# NIP_-DRIVE.net
KiCad netlist of a schematic drawn in Altium Designer
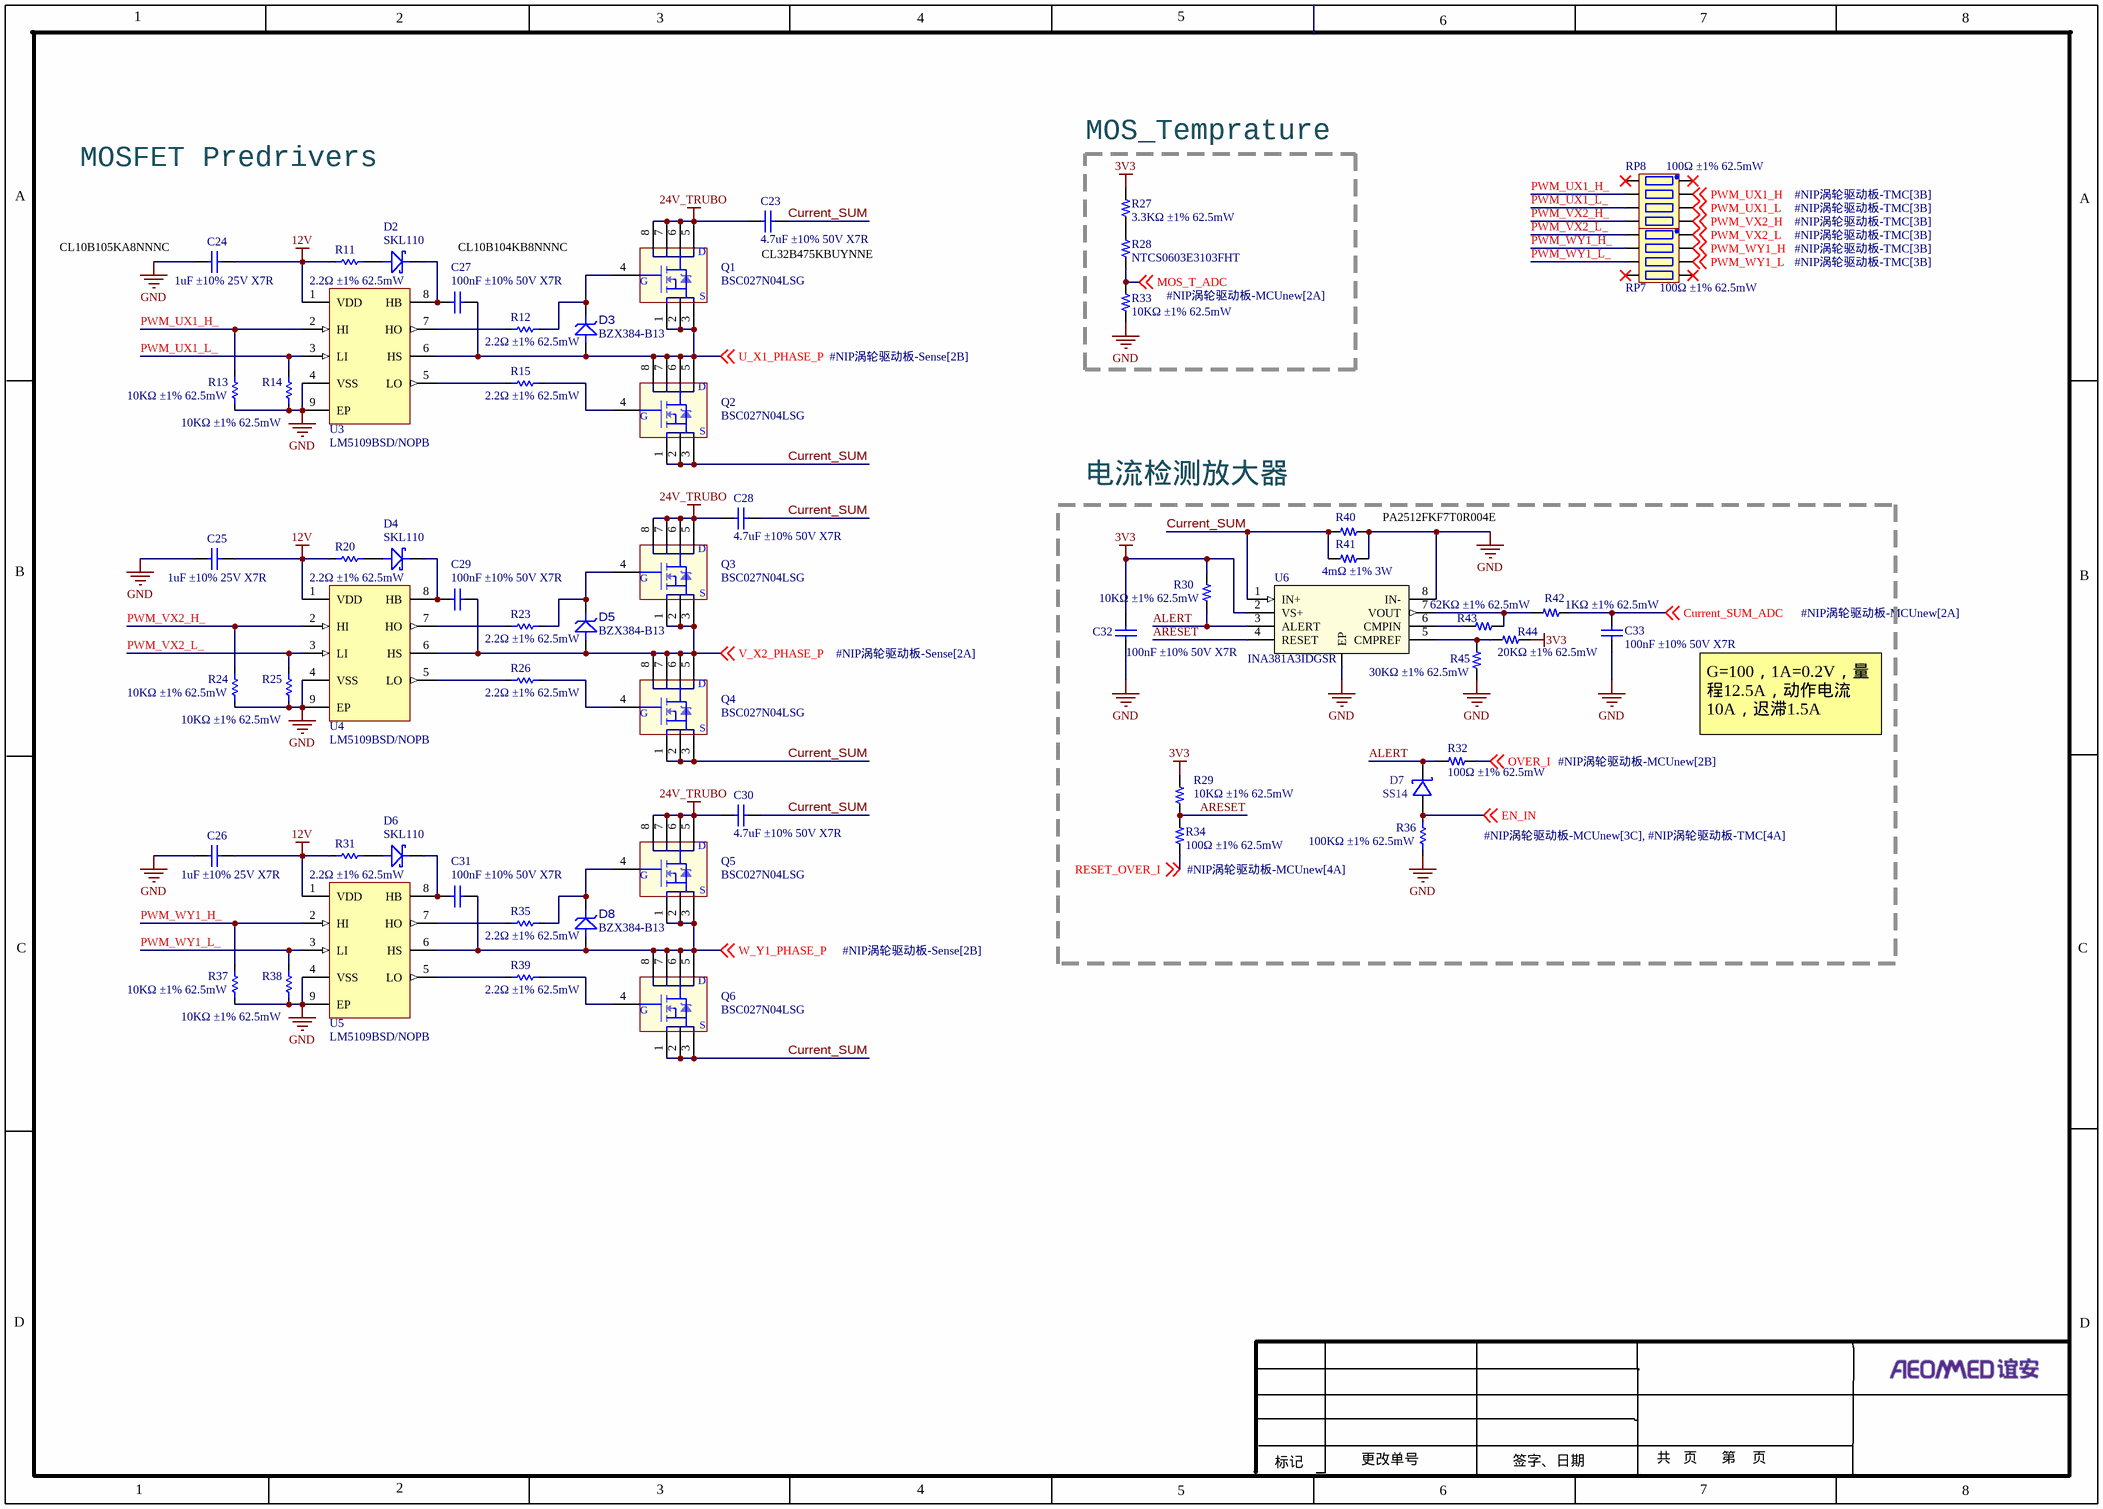
[diagram p0: #NIP涡轮驱动板-DRIVE.SchDoc]

(export (version "E")
  (design (tool "Eeschema 10.0.6"))
  (components
    (comp (ref "C23")
      (value "4.7uF ±10% 50V X7R")
      (footprint "C-1210")
      (description "CL32B475KBUYNNE")
      (libsource (lib "Device") (part "C-1210"))
    )
    (comp (ref "C24")
      (value "1uF ±10% 25V X7R")
      (footprint "C0603")
      (description "CL10B105KA8NNNC")
      (fields (field (name "PUBLISHER") "Altium Limited"))
      (libsource (lib "Component") (part "Cap"))
    )
    (comp (ref "C25")
      (value "1uF ±10% 25V X7R")
      (footprint "C0603")
      (description "CL10B105KA8NNNC")
      (fields (field (name "PUBLISHER") "Altium Limited"))
      (libsource (lib "Component") (part "Cap"))
    )
    (comp (ref "C26")
      (value "1uF ±10% 25V X7R")
      (footprint "C0603")
      (description "CL10B105KA8NNNC")
      (fields (field (name "PUBLISHER") "Altium Limited"))
      (libsource (lib "Component") (part "Cap"))
    )
    (comp (ref "C27")
      (value "100nF ±10% 50V X7R")
      (footprint "C-0603")
      (description "CL10B104KB8NNNC")
      (libsource (lib "Device") (part "C-0603"))
    )
    (comp (ref "C28")
      (value "4.7uF ±10% 50V X7R")
      (footprint "C-1210")
      (description "CL32B475KBUYNNE")
      (libsource (lib "Device") (part "C-1210"))
    )
    (comp (ref "C29")
      (value "100nF ±10% 50V X7R")
      (footprint "C-0603")
      (description "CL10B104KB8NNNC")
      (libsource (lib "Device") (part "C-0603"))
    )
    (comp (ref "C30")
      (value "4.7uF ±10% 50V X7R")
      (footprint "C-1210")
      (description "CL32B475KBUYNNE")
      (libsource (lib "Device") (part "C-1210"))
    )
    (comp (ref "C31")
      (value "100nF ±10% 50V X7R")
      (footprint "C-0603")
      (description "CL10B104KB8NNNC")
      (libsource (lib "Device") (part "C-0603"))
    )
    (comp (ref "C32")
      (value "100nF ±10% 50V X7R")
      (footprint "C0402")
      (description "Capacitor")
      (fields (field (name "PUBLISHER") "Altium Limited"))
      (libsource (lib "Component") (part "Cap"))
    )
    (comp (ref "C33")
      (value "100nF ±10% 50V X7R")
      (footprint "C0402")
      (description "Capacitor")
      (fields (field (name "PUBLISHER") "Altium Limited"))
      (libsource (lib "Component") (part "Cap"))
    )
    (comp (ref "D2")
      (value "SKL110")
      (footprint "SODFL370X140-2N")
      (description "品牌：DIOTEC，型号：SKL110，1A，100V，ROHS")
      (fields (field (name "MANUFACTURER") "Diotec  Semiconductor"))
      (libsource (lib "altium-import") (part "root_2_DIO-SCHOTTKY_"))
    )
    (comp (ref "D3")
      (value "BZX384-B13")
      (footprint "SOD2512X100N")
      (description "品牌：NXP，型号：BZX384-B13，13V，SOD-323，ROHS")
      (fields (field (name "MANUFACTURER") "Nexperia"))
      (libsource (lib "BLDC") (part "ZENER"))
    )
    (comp (ref "D4")
      (value "SKL110")
      (footprint "SODFL370X140-2N")
      (description "品牌：DIOTEC，型号：SKL110，1A，100V，ROHS")
      (fields (field (name "MANUFACTURER") "Diotec  Semiconductor"))
      (libsource (lib "altium-import") (part "root_2_DIO-SCHOTTKY_"))
    )
    (comp (ref "D5")
      (value "BZX384-B13")
      (footprint "SOD2512X100N")
      (description "品牌：NXP，型号：BZX384-B13，13V，SOD-323，ROHS")
      (fields (field (name "MANUFACTURER") "Nexperia"))
      (libsource (lib "BLDC") (part "ZENER"))
    )
    (comp (ref "D6")
      (value "SKL110")
      (footprint "SODFL370X140-2N")
      (description "品牌：DIOTEC，型号：SKL110，1A，100V，ROHS")
      (fields (field (name "MANUFACTURER") "Diotec  Semiconductor"))
      (libsource (lib "altium-import") (part "root_2_DIO-SCHOTTKY_"))
    )
    (comp (ref "D7")
      (value "SS14")
      (footprint "SOD-123_L2.7-W1.6-LS3.7-RD")
      (description "直流反向耐压(Vr):40V;平均整流电流(Io):3A;正向压降(Vf):500mV@3A;")
      (fields (field (name "MANUFACTURER") "DIODES(美台)") (field (name "MANUFACTURER PART") "B340A-13-F"))
      (libsource (lib "Component") (part "Diode_Schottky"))
    )
    (comp (ref "D8")
      (value "BZX384-B13")
      (footprint "SOD2512X100N")
      (description "品牌：NXP，型号：BZX384-B13，13V，SOD-323，ROHS")
      (fields (field (name "MANUFACTURER") "Nexperia"))
      (libsource (lib "BLDC") (part "ZENER"))
    )
    (comp (ref "Q1")
      (value "BSC027N04LSG")
      (footprint "PG-TDSON-8")
      (description "品牌：INFINEON，型号： BSC027N04LSG，40V，100A，ROHS")
      (libsource (lib "IC") (part "BSC027N04LS"))
    )
    (comp (ref "Q2")
      (value "BSC027N04LSG")
      (footprint "PG-TDSON-8")
      (description "品牌：INFINEON，型号： BSC027N04LSG，40V，100A，ROHS")
      (libsource (lib "IC") (part "BSC027N04LS"))
    )
    (comp (ref "Q3")
      (value "BSC027N04LSG")
      (footprint "PG-TDSON-8")
      (description "品牌：INFINEON，型号： BSC027N04LSG，40V，100A，ROHS")
      (libsource (lib "IC") (part "BSC027N04LS"))
    )
    (comp (ref "Q4")
      (value "BSC027N04LSG")
      (footprint "PG-TDSON-8")
      (description "品牌：INFINEON，型号： BSC027N04LSG，40V，100A，ROHS")
      (libsource (lib "IC") (part "BSC027N04LS"))
    )
    (comp (ref "Q5")
      (value "BSC027N04LSG")
      (footprint "PG-TDSON-8")
      (description "品牌：INFINEON，型号： BSC027N04LSG，40V，100A，ROHS")
      (libsource (lib "IC") (part "BSC027N04LS"))
    )
    (comp (ref "Q6")
      (value "BSC027N04LSG")
      (footprint "PG-TDSON-8")
      (description "品牌：INFINEON，型号： BSC027N04LSG，40V，100A，ROHS")
      (libsource (lib "IC") (part "BSC027N04LS"))
    )
    (comp (ref "R11")
      (value "2.2Ω ±1% 62.5mW")
      (footprint "R0402")
      (description "Resistor")
      (fields (field (name "PUBLISHER") "Altium Limited"))
      (libsource (lib "Component") (part "Res_0402"))
    )
    (comp (ref "R12")
      (value "2.2Ω ±1% 62.5mW")
      (footprint "R0402")
      (description "Resistor")
      (fields (field (name "PUBLISHER") "Altium Limited"))
      (libsource (lib "Component") (part "Res"))
    )
    (comp (ref "R13")
      (value "10KΩ ±1% 62.5mW")
      (footprint "R0402")
      (description "Resistor")
      (fields (field (name "PUBLISHER") "Altium Limited"))
      (libsource (lib "Component") (part "Res"))
    )
    (comp (ref "R14")
      (value "10KΩ ±1% 62.5mW")
      (footprint "R0402")
      (description "Resistor")
      (fields (field (name "PUBLISHER") "Altium Limited"))
      (libsource (lib "Component") (part "Res"))
    )
    (comp (ref "R15")
      (value "2.2Ω ±1% 62.5mW")
      (footprint "R0402")
      (description "Resistor")
      (fields (field (name "PUBLISHER") "Altium Limited"))
      (libsource (lib "Component") (part "Res"))
    )
    (comp (ref "R20")
      (value "2.2Ω ±1% 62.5mW")
      (footprint "R0402")
      (description "Resistor")
      (fields (field (name "PUBLISHER") "Altium Limited"))
      (libsource (lib "Component") (part "Res_0402"))
    )
    (comp (ref "R23")
      (value "2.2Ω ±1% 62.5mW")
      (footprint "R0402")
      (description "Resistor")
      (fields (field (name "PUBLISHER") "Altium Limited"))
      (libsource (lib "Component") (part "Res"))
    )
    (comp (ref "R24")
      (value "10KΩ ±1% 62.5mW")
      (footprint "R0402")
      (description "Resistor")
      (fields (field (name "PUBLISHER") "Altium Limited"))
      (libsource (lib "Component") (part "Res"))
    )
    (comp (ref "R25")
      (value "10KΩ ±1% 62.5mW")
      (footprint "R0402")
      (description "Resistor")
      (fields (field (name "PUBLISHER") "Altium Limited"))
      (libsource (lib "Component") (part "Res"))
    )
    (comp (ref "R26")
      (value "2.2Ω ±1% 62.5mW")
      (footprint "R0402")
      (description "Resistor")
      (fields (field (name "PUBLISHER") "Altium Limited"))
      (libsource (lib "Component") (part "Res"))
    )
    (comp (ref "R27")
      (value "3.3KΩ ±1% 62.5mW")
      (footprint "R0402")
      (libsource (lib "Device") (part "R-0603"))
    )
    (comp (ref "R28")
      (value "NTCS0603E3103FHT")
      (footprint "R-0603")
      (description "品牌：VISHAY，型号：NTCS0603E3103FHT，10K@25℃, 1%，B=3960,ROHS")
      (libsource (lib "Device") (part "R-0603"))
    )
    (comp (ref "R29")
      (value "10KΩ ±1% 62.5mW")
      (footprint "R0402")
      (libsource (lib "Device") (part "R-0603"))
    )
    (comp (ref "R30")
      (value "10KΩ ±1% 62.5mW")
      (footprint "R0402")
      (libsource (lib "Device") (part "R-0603"))
    )
    (comp (ref "R31")
      (value "2.2Ω ±1% 62.5mW")
      (footprint "R0402")
      (description "Resistor")
      (fields (field (name "PUBLISHER") "Altium Limited"))
      (libsource (lib "Component") (part "Res_0402"))
    )
    (comp (ref "R32")
      (value "100Ω ±1% 62.5mW")
      (footprint "R0402")
      (libsource (lib "Device") (part "R-0603"))
    )
    (comp (ref "R33")
      (value "10KΩ ±1% 62.5mW")
      (footprint "R0402")
      (libsource (lib "Device") (part "R-0603"))
    )
    (comp (ref "R34")
      (value "100Ω ±1% 62.5mW")
      (footprint "R0402")
      (libsource (lib "Device") (part "R-0603"))
    )
    (comp (ref "R35")
      (value "2.2Ω ±1% 62.5mW")
      (footprint "R0402")
      (description "Resistor")
      (fields (field (name "PUBLISHER") "Altium Limited"))
      (libsource (lib "Component") (part "Res"))
    )
    (comp (ref "R36")
      (value "100KΩ ±1% 62.5mW")
      (footprint "R0402")
      (description "RC0402FR-07100KL")
      (fields (field (name "PUBLISHER") "Altium Limited"))
      (libsource (lib "Component") (part "Res_0402"))
    )
    (comp (ref "R37")
      (value "10KΩ ±1% 62.5mW")
      (footprint "R0402")
      (description "Resistor")
      (fields (field (name "PUBLISHER") "Altium Limited"))
      (libsource (lib "Component") (part "Res"))
    )
    (comp (ref "R38")
      (value "10KΩ ±1% 62.5mW")
      (footprint "R0402")
      (description "Resistor")
      (fields (field (name "PUBLISHER") "Altium Limited"))
      (libsource (lib "Component") (part "Res"))
    )
    (comp (ref "R39")
      (value "2.2Ω ±1% 62.5mW")
      (footprint "R0402")
      (description "Resistor")
      (fields (field (name "PUBLISHER") "Altium Limited"))
      (libsource (lib "Component") (part "Res"))
    )
    (comp (ref "R40")
      (value "4mΩ ±1% 3W")
      (footprint "R-2512_4PIN")
      (description "PA2512FKF7T0R004E")
      (libsource (lib "Device") (part "R-2512"))
    )
    (comp (ref "R41")
      (value "4mΩ ±1% 3W")
      (footprint "R-2512_4PIN")
      (description "PA2512FKF7T0R004E")
      (libsource (lib "Device") (part "R-2512"))
    )
    (comp (ref "R42") (value "1KΩ ±1% 62.5mW") (footprint "R0402") (libsource (lib "Device") (part "R-0603")))
    (comp (ref "R43")
      (value "62KΩ ±1% 62.5mW")
      (footprint "R0402")
      (libsource (lib "Device") (part "R-0603"))
    )
    (comp (ref "R44")
      (value "20KΩ ±1% 62.5mW")
      (footprint "R0402")
      (libsource (lib "Device") (part "R-0603"))
    )
    (comp (ref "R45")
      (value "30KΩ ±1% 62.5mW")
      (footprint "R0402")
      (libsource (lib "Device") (part "R-0603"))
    )
    (comp (ref "RP7")
      (value "100Ω ±1% 62.5mW")
      (footprint "RES-ARRAY-SMD_0402-8P-L2.0-W1.0-BL")
      (libsource (lib "Device") (part "RP-0603"))
    )
    (comp (ref "RP8")
      (value "100Ω ±1% 62.5mW")
      (footprint "RES-ARRAY-SMD_0402-8P-L2.0-W1.0-BL")
      (libsource (lib "Device") (part "RP-0603"))
    )
    (comp (ref "U3")
      (value "LM5109BSD/NOPB")
      (footprint "PSON80P400X80_HS-9N")
      (description "品牌：TI，型号：LM5109BSD/NOPB，ROHS")
      (fields (field (name "MANUFACTURER") "Texas Instruments"))
      (libsource (lib "BLDC") (part "LM5109"))
    )
    (comp (ref "U4")
      (value "LM5109BSD/NOPB")
      (footprint "PSON80P400X80_HS-9N")
      (description "品牌：TI，型号：LM5109BSD/NOPB，ROHS")
      (fields (field (name "MANUFACTURER") "Texas Instruments"))
      (libsource (lib "BLDC") (part "LM5109"))
    )
    (comp (ref "U5")
      (value "LM5109BSD/NOPB")
      (footprint "PSON80P400X80_HS-9N")
      (description "品牌：TI，型号：LM5109BSD/NOPB，ROHS")
      (fields (field (name "MANUFACTURER") "Texas Instruments"))
      (libsource (lib "BLDC") (part "LM5109"))
    )
    (comp (ref "U6")
      (value "INA381A3IDGSR")
      (footprint "WSON-8_L2.0-W2.0-P0.50-BL-EP0.9")
      (description "品牌：TI，型号：INA381A1IDGSR，ROHS")
      (fields (field (name "COPYRIGHT") "Copyright (C) 2022 Ultra Librarian. All rights reserved."))
      (libsource (lib "all") (part "INA381A2IDSGR"))
    )
  )
  (nets
    (net (code "1") (name "/ALERT") (class "Default")
      (node (ref "D7") (pin "1") (pinfunction "K_1") (pintype "passive"))
      (node (ref "R30") (pin "2") (pinfunction "2_2") (pintype "passive"))
      (node (ref "R32") (pin "1") (pinfunction "1_1") (pintype "passive"))
      (node (ref "U6") (pin "3") (pinfunction "ALERT_3") (pintype "passive"))
    )
    (net (code "2") (name "/ARESET") (class "Default")
      (node (ref "R29") (pin "2") (pinfunction "2_2") (pintype "passive"))
      (node (ref "R34") (pin "1") (pinfunction "1_1") (pintype "passive"))
      (node (ref "U6") (pin "4") (pinfunction "RESET_4") (pintype "passive"))
    )
    (net (code "3") (name "/Current_SUM") (class "Default")
      (node (ref "C23") (pin "1") (pinfunction "1_1") (pintype "passive"))
      (node (ref "C28") (pin "1") (pinfunction "1_1") (pintype "passive"))
      (node (ref "C30") (pin "1") (pinfunction "1_1") (pintype "passive"))
      (node (ref "Q2") (pin "1") (pinfunction "S_1") (pintype "passive"))
      (node (ref "Q2") (pin "2") (pinfunction "S_2") (pintype "passive"))
      (node (ref "Q2") (pin "3") (pinfunction "S_3") (pintype "passive"))
      (node (ref "Q4") (pin "1") (pinfunction "S_1") (pintype "passive"))
      (node (ref "Q4") (pin "2") (pinfunction "S_2") (pintype "passive"))
      (node (ref "Q4") (pin "3") (pinfunction "S_3") (pintype "passive"))
      (node (ref "Q6") (pin "1") (pinfunction "S_1") (pintype "passive"))
      (node (ref "Q6") (pin "2") (pinfunction "S_2") (pintype "passive"))
      (node (ref "Q6") (pin "3") (pinfunction "S_3") (pintype "passive"))
      (node (ref "R40") (pin "2") (pinfunction "2_2") (pintype "passive"))
      (node (ref "R41") (pin "2") (pinfunction "2_2") (pintype "passive"))
      (node (ref "U6") (pin "1") (pinfunction "IN+_1") (pintype "input"))
    )
    (net (code "4") (name "/PWM_UX1_H_") (class "Default")
      (node (ref "R13") (pin "2") (pinfunction "2_2") (pintype "passive"))
      (node (ref "RP8") (pin "7") (pinfunction "7_7") (pintype "passive"))
      (node (ref "U3") (pin "2") (pinfunction "HI_2") (pintype "input"))
    )
    (net (code "5") (name "/PWM_UX1_L_") (class "Default")
      (node (ref "R14") (pin "2") (pinfunction "2_2") (pintype "passive"))
      (node (ref "RP8") (pin "6") (pinfunction "6_6") (pintype "passive"))
      (node (ref "U3") (pin "3") (pinfunction "LI_3") (pintype "input"))
    )
    (net (code "6") (name "/PWM_VX2_H_") (class "Default")
      (node (ref "R24") (pin "2") (pinfunction "2_2") (pintype "passive"))
      (node (ref "RP8") (pin "5") (pinfunction "5_5") (pintype "passive"))
      (node (ref "U4") (pin "2") (pinfunction "HI_2") (pintype "input"))
    )
    (net (code "7") (name "/PWM_VX2_L_") (class "Default")
      (node (ref "R25") (pin "2") (pinfunction "2_2") (pintype "passive"))
      (node (ref "RP7") (pin "8") (pinfunction "8_8") (pintype "passive"))
      (node (ref "U4") (pin "3") (pinfunction "LI_3") (pintype "input"))
    )
    (net (code "8") (name "/PWM_WY1_H_") (class "Default")
      (node (ref "R37") (pin "2") (pinfunction "2_2") (pintype "passive"))
      (node (ref "RP7") (pin "7") (pinfunction "7_7") (pintype "passive"))
      (node (ref "U5") (pin "2") (pinfunction "HI_2") (pintype "input"))
    )
    (net (code "9") (name "/PWM_WY1_L_") (class "Default")
      (node (ref "R38") (pin "2") (pinfunction "2_2") (pintype "passive"))
      (node (ref "RP7") (pin "6") (pinfunction "6_6") (pintype "passive"))
      (node (ref "U5") (pin "3") (pinfunction "LI_3") (pintype "input"))
    )
    (net (code "10") (name "3V3") (class "Default")
      (node (ref "C32") (pin "1") (pinfunction "1_1") (pintype "passive"))
      (node (ref "R27") (pin "2") (pinfunction "2_2") (pintype "passive"))
      (node (ref "R29") (pin "1") (pinfunction "1_1") (pintype "passive"))
      (node (ref "R30") (pin "1") (pinfunction "1_1") (pintype "passive"))
      (node (ref "R44") (pin "2") (pinfunction "2_2") (pintype "passive"))
      (node (ref "U6") (pin "2") (pinfunction "VS+_2") (pintype "passive"))
    )
    (net (code "11") (name "12V") (class "Default")
      (node (ref "C24") (pin "1") (pinfunction "1_1") (pintype "passive"))
      (node (ref "C25") (pin "1") (pinfunction "1_1") (pintype "passive"))
      (node (ref "C26") (pin "1") (pinfunction "1_1") (pintype "passive"))
      (node (ref "R11") (pin "1") (pinfunction "1_1") (pintype "passive"))
      (node (ref "R20") (pin "1") (pinfunction "1_1") (pintype "passive"))
      (node (ref "R31") (pin "1") (pinfunction "1_1") (pintype "passive"))
      (node (ref "U3") (pin "1") (pinfunction "VDD_1") (pintype "power_in"))
      (node (ref "U4") (pin "1") (pinfunction "VDD_1") (pintype "power_in"))
      (node (ref "U5") (pin "1") (pinfunction "VDD_1") (pintype "power_in"))
    )
    (net (code "12") (name "24V_TRUBO") (class "Default")
      (node (ref "C23") (pin "2") (pinfunction "2_2") (pintype "passive"))
      (node (ref "C28") (pin "2") (pinfunction "2_2") (pintype "passive"))
      (node (ref "C30") (pin "2") (pinfunction "2_2") (pintype "passive"))
      (node (ref "Q1") (pin "5") (pinfunction "D_5") (pintype "passive"))
      (node (ref "Q1") (pin "6") (pinfunction "D_6") (pintype "passive"))
      (node (ref "Q1") (pin "7") (pinfunction "D_7") (pintype "passive"))
      (node (ref "Q1") (pin "8") (pinfunction "D_8") (pintype "passive"))
      (node (ref "Q3") (pin "5") (pinfunction "D_5") (pintype "passive"))
      (node (ref "Q3") (pin "6") (pinfunction "D_6") (pintype "passive"))
      (node (ref "Q3") (pin "7") (pinfunction "D_7") (pintype "passive"))
      (node (ref "Q3") (pin "8") (pinfunction "D_8") (pintype "passive"))
      (node (ref "Q5") (pin "5") (pinfunction "D_5") (pintype "passive"))
      (node (ref "Q5") (pin "6") (pinfunction "D_6") (pintype "passive"))
      (node (ref "Q5") (pin "7") (pinfunction "D_7") (pintype "passive"))
      (node (ref "Q5") (pin "8") (pinfunction "D_8") (pintype "passive"))
    )
    (net (code "13") (name "Current_SUM_ADC") (class "Default")
      (node (ref "C33") (pin "2") (pinfunction "2_2") (pintype "passive"))
      (node (ref "R42") (pin "2") (pinfunction "2_2") (pintype "passive"))
    )
    (net (code "14") (name "EN_IN") (class "Default")
      (node (ref "D7") (pin "2") (pinfunction "A_2") (pintype "passive"))
      (node (ref "R36") (pin "1") (pinfunction "1_1") (pintype "passive"))
    )
    (net (code "15") (name "GND") (class "Default")
      (node (ref "C24") (pin "2") (pinfunction "2_2") (pintype "passive"))
      (node (ref "C25") (pin "2") (pinfunction "2_2") (pintype "passive"))
      (node (ref "C26") (pin "2") (pinfunction "2_2") (pintype "passive"))
      (node (ref "C32") (pin "2") (pinfunction "2_2") (pintype "passive"))
      (node (ref "C33") (pin "1") (pinfunction "1_1") (pintype "passive"))
      (node (ref "R13") (pin "1") (pinfunction "1_1") (pintype "passive"))
      (node (ref "R14") (pin "1") (pinfunction "1_1") (pintype "passive"))
      (node (ref "R24") (pin "1") (pinfunction "1_1") (pintype "passive"))
      (node (ref "R25") (pin "1") (pinfunction "1_1") (pintype "passive"))
      (node (ref "R33") (pin "1") (pinfunction "1_1") (pintype "passive"))
      (node (ref "R36") (pin "2") (pinfunction "2_2") (pintype "passive"))
      (node (ref "R37") (pin "1") (pinfunction "1_1") (pintype "passive"))
      (node (ref "R38") (pin "1") (pinfunction "1_1") (pintype "passive"))
      (node (ref "R40") (pin "1") (pinfunction "1_1") (pintype "passive"))
      (node (ref "R41") (pin "1") (pinfunction "1_1") (pintype "passive"))
      (node (ref "R45") (pin "1") (pinfunction "1_1") (pintype "passive"))
      (node (ref "U3") (pin "4") (pinfunction "VSS_4") (pintype "power_in"))
      (node (ref "U3") (pin "9") (pinfunction "EP_9") (pintype "passive"))
      (node (ref "U4") (pin "4") (pinfunction "VSS_4") (pintype "power_in"))
      (node (ref "U4") (pin "9") (pinfunction "EP_9") (pintype "passive"))
      (node (ref "U5") (pin "4") (pinfunction "VSS_4") (pintype "power_in"))
      (node (ref "U5") (pin "9") (pinfunction "EP_9") (pintype "passive"))
      (node (ref "U6") (pin "8") (pinfunction "IN-_8") (pintype "passive"))
      (node (ref "U6") (pin "9") (pinfunction "EP_9") (pintype "passive"))
    )
    (net (code "16") (name "MOS_T_ADC") (class "Default")
      (node (ref "R28") (pin "1") (pinfunction "1_1") (pintype "passive"))
      (node (ref "R33") (pin "2") (pinfunction "2_2") (pintype "passive"))
    )
    (net (code "17") (name "Net-(D2-Pad2)") (class "Default")
      (node (ref "D2") (pin "2") (pinfunction "2_2") (pintype "passive"))
      (node (ref "R11") (pin "2") (pinfunction "2_2") (pintype "passive"))
    )
    (net (code "18") (name "Net-(D3-K)") (class "Default")
      (node (ref "D3") (pin "1") (pinfunction "K_1") (pintype "passive"))
      (node (ref "Q1") (pin "4") (pinfunction "G_4") (pintype "passive"))
      (node (ref "R12") (pin "2") (pinfunction "2_2") (pintype "passive"))
    )
    (net (code "19") (name "Net-(D4-Pad2)") (class "Default")
      (node (ref "D4") (pin "2") (pinfunction "2_2") (pintype "passive"))
      (node (ref "R20") (pin "2") (pinfunction "2_2") (pintype "passive"))
    )
    (net (code "20") (name "Net-(D5-K)") (class "Default")
      (node (ref "D5") (pin "1") (pinfunction "K_1") (pintype "passive"))
      (node (ref "Q3") (pin "4") (pinfunction "G_4") (pintype "passive"))
      (node (ref "R23") (pin "2") (pinfunction "2_2") (pintype "passive"))
    )
    (net (code "21") (name "Net-(D6-Pad2)") (class "Default")
      (node (ref "D6") (pin "2") (pinfunction "2_2") (pintype "passive"))
      (node (ref "R31") (pin "2") (pinfunction "2_2") (pintype "passive"))
    )
    (net (code "22") (name "Net-(D8-K)") (class "Default")
      (node (ref "D8") (pin "1") (pinfunction "K_1") (pintype "passive"))
      (node (ref "Q5") (pin "4") (pinfunction "G_4") (pintype "passive"))
      (node (ref "R35") (pin "2") (pinfunction "2_2") (pintype "passive"))
    )
    (net (code "23") (name "Net-(Q2-G)") (class "Default")
      (node (ref "Q2") (pin "4") (pinfunction "G_4") (pintype "passive"))
      (node (ref "R15") (pin "2") (pinfunction "2_2") (pintype "passive"))
    )
    (net (code "24") (name "Net-(Q4-G)") (class "Default")
      (node (ref "Q4") (pin "4") (pinfunction "G_4") (pintype "passive"))
      (node (ref "R26") (pin "2") (pinfunction "2_2") (pintype "passive"))
    )
    (net (code "25") (name "Net-(Q6-G)") (class "Default")
      (node (ref "Q6") (pin "4") (pinfunction "G_4") (pintype "passive"))
      (node (ref "R39") (pin "2") (pinfunction "2_2") (pintype "passive"))
    )
    (net (code "26") (name "Net-(R27-Pad1)") (class "Default")
      (node (ref "R27") (pin "1") (pinfunction "1_1") (pintype "passive"))
      (node (ref "R28") (pin "2") (pinfunction "2_2") (pintype "passive"))
    )
    (net (code "27") (name "Net-(U3-HB)") (class "Default")
      (node (ref "C27") (pin "2") (pinfunction "2_2") (pintype "passive"))
      (node (ref "D2") (pin "1") (pinfunction "1_1") (pintype "passive"))
      (node (ref "U3") (pin "8") (pinfunction "HB_8") (pintype "power_in"))
    )
    (net (code "28") (name "Net-(U3-HO)") (class "Default")
      (node (ref "R12") (pin "1") (pinfunction "1_1") (pintype "passive"))
      (node (ref "U3") (pin "7") (pinfunction "HO_7") (pintype "output"))
    )
    (net (code "29") (name "Net-(U3-LO)") (class "Default")
      (node (ref "R15") (pin "1") (pinfunction "1_1") (pintype "passive"))
      (node (ref "U3") (pin "5") (pinfunction "LO_5") (pintype "output"))
    )
    (net (code "30") (name "Net-(U4-HB)") (class "Default")
      (node (ref "C29") (pin "2") (pinfunction "2_2") (pintype "passive"))
      (node (ref "D4") (pin "1") (pinfunction "1_1") (pintype "passive"))
      (node (ref "U4") (pin "8") (pinfunction "HB_8") (pintype "power_in"))
    )
    (net (code "31") (name "Net-(U4-HO)") (class "Default")
      (node (ref "R23") (pin "1") (pinfunction "1_1") (pintype "passive"))
      (node (ref "U4") (pin "7") (pinfunction "HO_7") (pintype "output"))
    )
    (net (code "32") (name "Net-(U4-LO)") (class "Default")
      (node (ref "R26") (pin "1") (pinfunction "1_1") (pintype "passive"))
      (node (ref "U4") (pin "5") (pinfunction "LO_5") (pintype "output"))
    )
    (net (code "33") (name "Net-(U5-HB)") (class "Default")
      (node (ref "C31") (pin "2") (pinfunction "2_2") (pintype "passive"))
      (node (ref "D6") (pin "1") (pinfunction "1_1") (pintype "passive"))
      (node (ref "U5") (pin "8") (pinfunction "HB_8") (pintype "power_in"))
    )
    (net (code "34") (name "Net-(U5-HO)") (class "Default")
      (node (ref "R35") (pin "1") (pinfunction "1_1") (pintype "passive"))
      (node (ref "U5") (pin "7") (pinfunction "HO_7") (pintype "output"))
    )
    (net (code "35") (name "Net-(U5-LO)") (class "Default")
      (node (ref "R39") (pin "1") (pinfunction "1_1") (pintype "passive"))
      (node (ref "U5") (pin "5") (pinfunction "LO_5") (pintype "output"))
    )
    (net (code "36") (name "Net-(U6-CMPIN)") (class "Default")
      (node (ref "R43") (pin "1") (pinfunction "1_1") (pintype "passive"))
      (node (ref "U6") (pin "6") (pinfunction "CMPIN_6") (pintype "passive"))
    )
    (net (code "37") (name "Net-(U6-CMPREF)") (class "Default")
      (node (ref "R44") (pin "1") (pinfunction "1_1") (pintype "passive"))
      (node (ref "R45") (pin "2") (pinfunction "2_2") (pintype "passive"))
      (node (ref "U6") (pin "5") (pinfunction "CMPREF_5") (pintype "passive"))
    )
    (net (code "38") (name "Net-(U6-VOUT)") (class "Default")
      (node (ref "R42") (pin "1") (pinfunction "1_1") (pintype "passive"))
      (node (ref "R43") (pin "2") (pinfunction "2_2") (pintype "passive"))
      (node (ref "U6") (pin "7") (pinfunction "VOUT_7") (pintype "output"))
    )
    (net (code "39") (name "OVER_I") (class "Default")
      (node (ref "R32") (pin "2") (pinfunction "2_2") (pintype "passive"))
    )
    (net (code "40") (name "PWM_UX1_H") (class "Default")
      (node (ref "RP8") (pin "2") (pinfunction "2_2") (pintype "passive"))
    )
    (net (code "41") (name "PWM_UX1_L") (class "Default")
      (node (ref "RP8") (pin "3") (pinfunction "3_3") (pintype "passive"))
    )
    (net (code "42") (name "PWM_VX2_H") (class "Default")
      (node (ref "RP8") (pin "4") (pinfunction "4_4") (pintype "passive"))
    )
    (net (code "43") (name "PWM_VX2_L") (class "Default")
      (node (ref "RP7") (pin "1") (pinfunction "1_1") (pintype "passive"))
    )
    (net (code "44") (name "PWM_WY1_H") (class "Default")
      (node (ref "RP7") (pin "2") (pinfunction "2_2") (pintype "passive"))
    )
    (net (code "45") (name "PWM_WY1_L") (class "Default")
      (node (ref "RP7") (pin "3") (pinfunction "3_3") (pintype "passive"))
    )
    (net (code "46") (name "RESET_OVER_I") (class "Default")
      (node (ref "R34") (pin "2") (pinfunction "2_2") (pintype "passive"))
    )
    (net (code "47") (name "U_X1_PHASE_P") (class "Default")
      (node (ref "C27") (pin "1") (pinfunction "1_1") (pintype "passive"))
      (node (ref "D3") (pin "2") (pinfunction "A_2") (pintype "passive"))
      (node (ref "Q1") (pin "1") (pinfunction "S_1") (pintype "passive"))
      (node (ref "Q1") (pin "2") (pinfunction "S_2") (pintype "passive"))
      (node (ref "Q1") (pin "3") (pinfunction "S_3") (pintype "passive"))
      (node (ref "Q2") (pin "5") (pinfunction "D_5") (pintype "passive"))
      (node (ref "Q2") (pin "6") (pinfunction "D_6") (pintype "passive"))
      (node (ref "Q2") (pin "7") (pinfunction "D_7") (pintype "passive"))
      (node (ref "Q2") (pin "8") (pinfunction "D_8") (pintype "passive"))
      (node (ref "U3") (pin "6") (pinfunction "HS_6") (pintype "passive"))
    )
    (net (code "48") (name "V_X2_PHASE_P") (class "Default")
      (node (ref "C29") (pin "1") (pinfunction "1_1") (pintype "passive"))
      (node (ref "D5") (pin "2") (pinfunction "A_2") (pintype "passive"))
      (node (ref "Q3") (pin "1") (pinfunction "S_1") (pintype "passive"))
      (node (ref "Q3") (pin "2") (pinfunction "S_2") (pintype "passive"))
      (node (ref "Q3") (pin "3") (pinfunction "S_3") (pintype "passive"))
      (node (ref "Q4") (pin "5") (pinfunction "D_5") (pintype "passive"))
      (node (ref "Q4") (pin "6") (pinfunction "D_6") (pintype "passive"))
      (node (ref "Q4") (pin "7") (pinfunction "D_7") (pintype "passive"))
      (node (ref "Q4") (pin "8") (pinfunction "D_8") (pintype "passive"))
      (node (ref "U4") (pin "6") (pinfunction "HS_6") (pintype "passive"))
    )
    (net (code "49") (name "W_Y1_PHASE_P") (class "Default")
      (node (ref "C31") (pin "1") (pinfunction "1_1") (pintype "passive"))
      (node (ref "D8") (pin "2") (pinfunction "A_2") (pintype "passive"))
      (node (ref "Q5") (pin "1") (pinfunction "S_1") (pintype "passive"))
      (node (ref "Q5") (pin "2") (pinfunction "S_2") (pintype "passive"))
      (node (ref "Q5") (pin "3") (pinfunction "S_3") (pintype "passive"))
      (node (ref "Q6") (pin "5") (pinfunction "D_5") (pintype "passive"))
      (node (ref "Q6") (pin "6") (pinfunction "D_6") (pintype "passive"))
      (node (ref "Q6") (pin "7") (pinfunction "D_7") (pintype "passive"))
      (node (ref "Q6") (pin "8") (pinfunction "D_8") (pintype "passive"))
      (node (ref "U5") (pin "6") (pinfunction "HS_6") (pintype "passive"))
    )
    (net (code "50") (name "unconnected-(RP7-Pad4)") (class "Default")
      (node (ref "RP7") (pin "4") (pinfunction "4_4") (pintype "passive+no_connect"))
    )
    (net (code "51") (name "unconnected-(RP7-Pad5)") (class "Default")
      (node (ref "RP7") (pin "5") (pinfunction "5_5") (pintype "passive+no_connect"))
    )
    (net (code "52") (name "unconnected-(RP8-Pad1)") (class "Default")
      (node (ref "RP8") (pin "1") (pinfunction "1_1") (pintype "passive+no_connect"))
    )
    (net (code "53") (name "unconnected-(RP8-Pad8)") (class "Default")
      (node (ref "RP8") (pin "8") (pinfunction "8_8") (pintype "passive+no_connect"))
    )
  )
)
